# minime_2_1_1-a.net
KiCad netlist of a schematic drawn in EAGLE
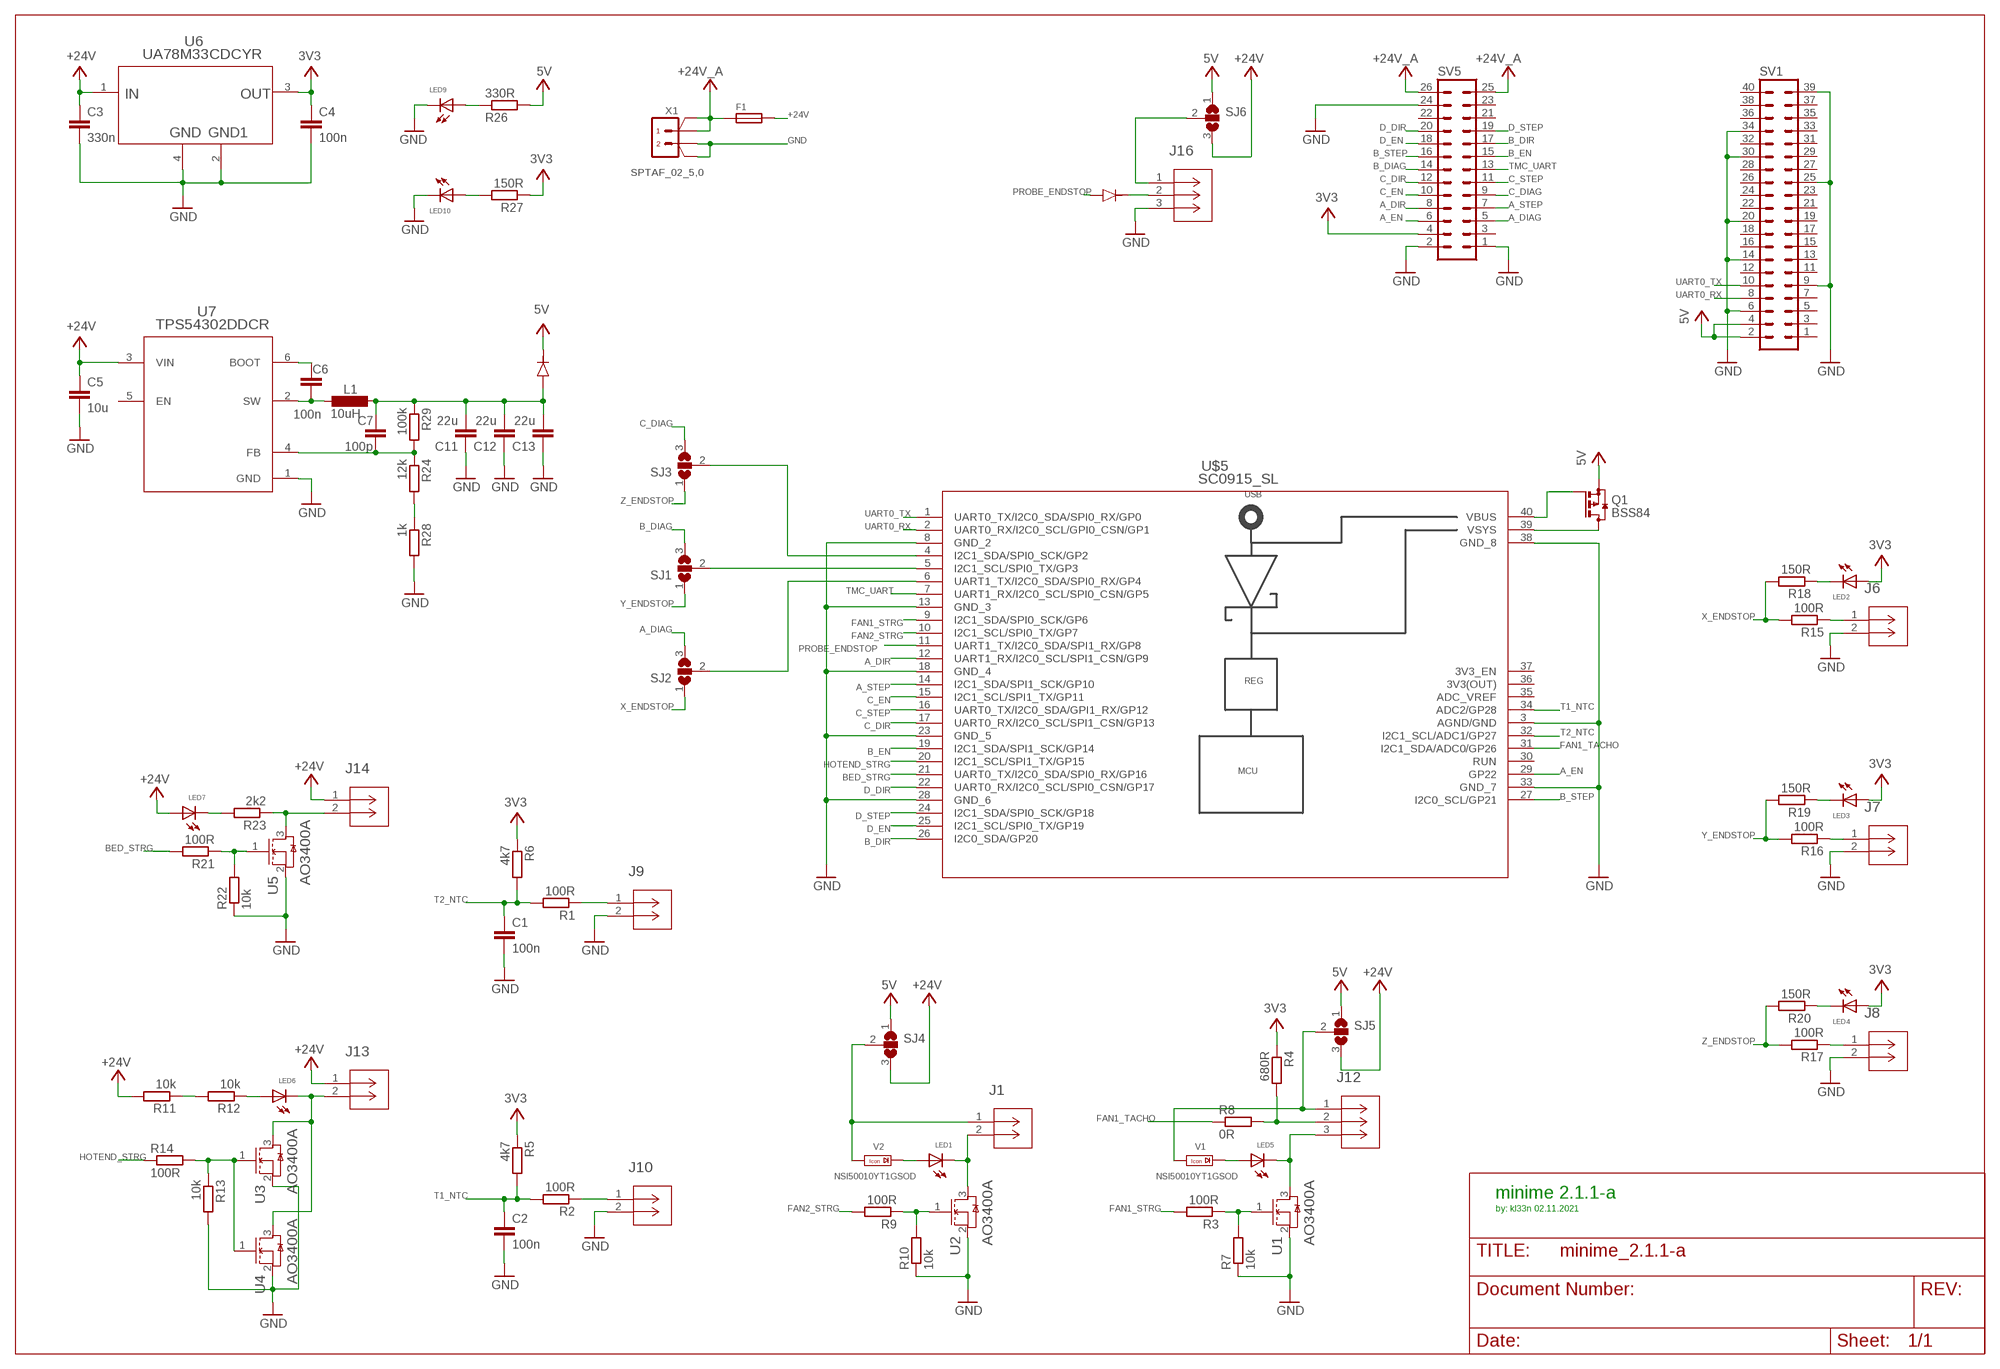
[diagram p0: schematic, sheet 1]

(export (version "E")
  (design (tool "Eeschema 10.0.6"))
  (components
    (comp (ref "C1")
      (value "100n")
      (footprint "eagle-import:C0603")
      (libsource (lib "eagle-import") (part "C-EUC0603"))
    )
    (comp (ref "C2")
      (value "100n")
      (footprint "eagle-import:C0603")
      (libsource (lib "eagle-import") (part "C-EUC0603"))
    )
    (comp (ref "C3")
      (value "330n")
      (footprint "eagle-import:C0603")
      (libsource (lib "eagle-import") (part "C-EUC0603"))
    )
    (comp (ref "C4")
      (value "100n")
      (footprint "eagle-import:C0603")
      (libsource (lib "eagle-import") (part "C-EUC0603"))
    )
    (comp (ref "C5")
      (value "10u")
      (footprint "eagle-import:C0603")
      (libsource (lib "eagle-import") (part "C-EUC0603"))
    )
    (comp (ref "C6")
      (value "100n")
      (footprint "eagle-import:C0603")
      (libsource (lib "eagle-import") (part "C-EUC0603"))
    )
    (comp (ref "C7")
      (value "100p")
      (footprint "eagle-import:C0603")
      (libsource (lib "eagle-import") (part "C-EUC0603"))
    )
    (comp (ref "C11")
      (value "22u")
      (footprint "eagle-import:C1210K")
      (libsource (lib "eagle-import") (part "C-EUC1210K"))
    )
    (comp (ref "C12")
      (value "22u")
      (footprint "eagle-import:C1210K")
      (libsource (lib "eagle-import") (part "C-EUC1210K"))
    )
    (comp (ref "C13")
      (value "22u")
      (footprint "eagle-import:C1210K")
      (libsource (lib "eagle-import") (part "C-EUC1210K"))
    )
    (comp (ref "CR1")
      (value "SS54")
      (footprint "eagle-import:DIODE_DO214AC")
      (fields
        (field (name "MANUFACTURER_PART_NUMBER") "SS14-E3/5AT")
        (field (name "COPYRIGHT") "Copyright (C) 2021 Ultra Librarian. All rights reserved.")
      )
      (libsource (lib "eagle-import") (part "SS14-E3/5AT"))
    )
    (comp (ref "CR2")
      (value "SS14")
      (footprint "eagle-import:DIODE_DO214AC")
      (fields
        (field (name "MANUFACTURER_PART_NUMBER") "SS14-E3/5AT")
        (field (name "COPYRIGHT") "Copyright (C) 2021 Ultra Librarian. All rights reserved.")
      )
      (libsource (lib "eagle-import") (part "SS14-E3/5AT"))
    )
    (comp (ref "F1")
      (value "FUSE/SERIE154")
      (footprint "eagle-import:FUSE_NANO-OMNI")
      (libsource (lib "eagle-import") (part "FUSE/SERIE154"))
    )
    (comp (ref "J1")
      (value "B2B-XH-A(LF)(SN)")
      (footprint "eagle-import:CONN_B2B-XH-A(LF)(SN)_JST")
      (fields (field (name "COPYRIGHT") "Copyright (C) 2018 Accelerated Designs. All rights reserved"))
      (libsource (lib "eagle-import") (part "B2B-XH-A(LF)(SN)"))
    )
    (comp (ref "J6")
      (value "B2B-XH-A(LF)(SN)")
      (footprint "eagle-import:CONN_B2B-XH-A(LF)(SN)_JST")
      (fields (field (name "COPYRIGHT") "Copyright (C) 2018 Accelerated Designs. All rights reserved"))
      (libsource (lib "eagle-import") (part "B2B-XH-A(LF)(SN)"))
    )
    (comp (ref "J7")
      (value "B2B-XH-A(LF)(SN)")
      (footprint "eagle-import:CONN_B2B-XH-A(LF)(SN)_JST")
      (fields (field (name "COPYRIGHT") "Copyright (C) 2018 Accelerated Designs. All rights reserved"))
      (libsource (lib "eagle-import") (part "B2B-XH-A(LF)(SN)"))
    )
    (comp (ref "J8")
      (value "B2B-XH-A(LF)(SN)")
      (footprint "eagle-import:CONN_B2B-XH-A(LF)(SN)_JST")
      (fields (field (name "COPYRIGHT") "Copyright (C) 2018 Accelerated Designs. All rights reserved"))
      (libsource (lib "eagle-import") (part "B2B-XH-A(LF)(SN)"))
    )
    (comp (ref "J9")
      (value "B2B-XH-A(LF)(SN)")
      (footprint "eagle-import:CONN_B2B-XH-A(LF)(SN)_JST")
      (fields (field (name "COPYRIGHT") "Copyright (C) 2018 Accelerated Designs. All rights reserved"))
      (libsource (lib "eagle-import") (part "B2B-XH-A(LF)(SN)"))
    )
    (comp (ref "J10")
      (value "B2B-XH-A(LF)(SN)")
      (footprint "eagle-import:CONN_B2B-XH-A(LF)(SN)_JST")
      (fields (field (name "COPYRIGHT") "Copyright (C) 2018 Accelerated Designs. All rights reserved"))
      (libsource (lib "eagle-import") (part "B2B-XH-A(LF)(SN)"))
    )
    (comp (ref "J12")
      (value "B3B-XH-A(LF)(SN)")
      (footprint "eagle-import:CONN_B3B-XH-A_JST")
      (fields (field (name "COPYRIGHT") "Copyright (C) 2018 Accelerated Designs. All rights reserved"))
      (libsource (lib "eagle-import") (part "B3B-XH-A(LF)(SN)"))
    )
    (comp (ref "J13")
      (value "B2B-XH-A(LF)(SN)")
      (footprint "eagle-import:CONN_B2B-XH-A(LF)(SN)_JST")
      (fields (field (name "COPYRIGHT") "Copyright (C) 2018 Accelerated Designs. All rights reserved"))
      (libsource (lib "eagle-import") (part "B2B-XH-A(LF)(SN)"))
    )
    (comp (ref "J14")
      (value "B2B-XH-A(LF)(SN)")
      (footprint "eagle-import:CONN_B2B-XH-A(LF)(SN)_JST")
      (fields (field (name "COPYRIGHT") "Copyright (C) 2018 Accelerated Designs. All rights reserved"))
      (libsource (lib "eagle-import") (part "B2B-XH-A(LF)(SN)"))
    )
    (comp (ref "J16")
      (value "B3B-XH-A(LF)(SN)")
      (footprint "eagle-import:CONN_B3B-XH-A_JST")
      (fields (field (name "COPYRIGHT") "Copyright (C) 2018 Accelerated Designs. All rights reserved"))
      (libsource (lib "eagle-import") (part "B3B-XH-A(LF)(SN)"))
    )
    (comp (ref "L1")
      (value "10uH")
      (footprint "eagle-import:POWER-CHOKE_WE-TPC")
      (libsource (lib "eagle-import") (part "L-EUWE-TPC"))
    )
    (comp (ref "LED1")
      (value "LEDCHIP-LED0603")
      (footprint "eagle-import:CHIP-LED0603")
      (libsource (lib "eagle-import") (part "LEDCHIP-LED0603"))
    )
    (comp (ref "LED2")
      (value "LEDCHIP-LED0603")
      (footprint "eagle-import:CHIP-LED0603")
      (libsource (lib "eagle-import") (part "LEDCHIP-LED0603"))
    )
    (comp (ref "LED3")
      (value "LEDCHIP-LED0603")
      (footprint "eagle-import:CHIP-LED0603")
      (libsource (lib "eagle-import") (part "LEDCHIP-LED0603"))
    )
    (comp (ref "LED4")
      (value "LEDCHIP-LED0603")
      (footprint "eagle-import:CHIP-LED0603")
      (libsource (lib "eagle-import") (part "LEDCHIP-LED0603"))
    )
    (comp (ref "LED5")
      (value "LEDCHIP-LED0603")
      (footprint "eagle-import:CHIP-LED0603")
      (libsource (lib "eagle-import") (part "LEDCHIP-LED0603"))
    )
    (comp (ref "LED6")
      (value "LEDCHIP-LED0603")
      (footprint "eagle-import:CHIP-LED0603")
      (libsource (lib "eagle-import") (part "LEDCHIP-LED0603"))
    )
    (comp (ref "LED7")
      (value "LEDCHIP-LED0603")
      (footprint "eagle-import:CHIP-LED0603")
      (libsource (lib "eagle-import") (part "LEDCHIP-LED0603"))
    )
    (comp (ref "LED9")
      (value "LEDCHIP-LED0603")
      (footprint "eagle-import:CHIP-LED0603")
      (libsource (lib "eagle-import") (part "LEDCHIP-LED0603"))
    )
    (comp (ref "LED10")
      (value "LEDCHIP-LED0603")
      (footprint "eagle-import:CHIP-LED0603")
      (libsource (lib "eagle-import") (part "LEDCHIP-LED0603"))
    )
    (comp (ref "Q1")
      (value "BSS84")
      (footprint "eagle-import:SOT23")
      (libsource (lib "eagle-import") (part "BSS84"))
    )
    (comp (ref "R1")
      (value "100R")
      (footprint "eagle-import:R0603")
      (libsource (lib "eagle-import") (part "R-EU_R0603"))
    )
    (comp (ref "R2")
      (value "100R")
      (footprint "eagle-import:R0603")
      (libsource (lib "eagle-import") (part "R-EU_R0603"))
    )
    (comp (ref "R3")
      (value "100R")
      (footprint "eagle-import:R0603")
      (libsource (lib "eagle-import") (part "R-EU_R0603"))
    )
    (comp (ref "R4")
      (value "680R")
      (footprint "eagle-import:R0603")
      (libsource (lib "eagle-import") (part "R-EU_R0603"))
    )
    (comp (ref "R5")
      (value "4k7")
      (footprint "eagle-import:R0603")
      (libsource (lib "eagle-import") (part "R-EU_R0603"))
    )
    (comp (ref "R6")
      (value "4k7")
      (footprint "eagle-import:R0603")
      (libsource (lib "eagle-import") (part "R-EU_R0603"))
    )
    (comp (ref "R7")
      (value "10k")
      (footprint "eagle-import:R0603")
      (libsource (lib "eagle-import") (part "R-EU_R0603"))
    )
    (comp (ref "R8")
      (value "0R")
      (footprint "eagle-import:R0603")
      (libsource (lib "eagle-import") (part "R-EU_R0603"))
    )
    (comp (ref "R9")
      (value "100R")
      (footprint "eagle-import:R0603")
      (libsource (lib "eagle-import") (part "R-EU_R0603"))
    )
    (comp (ref "R10")
      (value "10k")
      (footprint "eagle-import:R0603")
      (libsource (lib "eagle-import") (part "R-EU_R0603"))
    )
    (comp (ref "R11")
      (value "10k")
      (footprint "eagle-import:R0603")
      (libsource (lib "eagle-import") (part "R-EU_R0603"))
    )
    (comp (ref "R12")
      (value "10k")
      (footprint "eagle-import:R0603")
      (libsource (lib "eagle-import") (part "R-EU_R0603"))
    )
    (comp (ref "R13")
      (value "10k")
      (footprint "eagle-import:R0603")
      (libsource (lib "eagle-import") (part "R-EU_R0603"))
    )
    (comp (ref "R14")
      (value "100R")
      (footprint "eagle-import:R0603")
      (libsource (lib "eagle-import") (part "R-EU_R0603"))
    )
    (comp (ref "R15")
      (value "100R")
      (footprint "eagle-import:R0603")
      (libsource (lib "eagle-import") (part "R-EU_R0603"))
    )
    (comp (ref "R16")
      (value "100R")
      (footprint "eagle-import:R0603")
      (libsource (lib "eagle-import") (part "R-EU_R0603"))
    )
    (comp (ref "R17")
      (value "100R")
      (footprint "eagle-import:R0603")
      (libsource (lib "eagle-import") (part "R-EU_R0603"))
    )
    (comp (ref "R18")
      (value "150R")
      (footprint "eagle-import:R0603")
      (libsource (lib "eagle-import") (part "R-EU_R0603"))
    )
    (comp (ref "R19")
      (value "150R")
      (footprint "eagle-import:R0603")
      (libsource (lib "eagle-import") (part "R-EU_R0603"))
    )
    (comp (ref "R20")
      (value "150R")
      (footprint "eagle-import:R0603")
      (libsource (lib "eagle-import") (part "R-EU_R0603"))
    )
    (comp (ref "R21")
      (value "100R")
      (footprint "eagle-import:R0603")
      (libsource (lib "eagle-import") (part "R-EU_R0603"))
    )
    (comp (ref "R22")
      (value "10k")
      (footprint "eagle-import:R0603")
      (libsource (lib "eagle-import") (part "R-EU_R0603"))
    )
    (comp (ref "R23")
      (value "2k2")
      (footprint "eagle-import:R0603")
      (libsource (lib "eagle-import") (part "R-EU_R0603"))
    )
    (comp (ref "R24")
      (value "12k")
      (footprint "eagle-import:R0603")
      (libsource (lib "eagle-import") (part "R-EU_R0603"))
    )
    (comp (ref "R26")
      (value "330R")
      (footprint "eagle-import:R0603")
      (libsource (lib "eagle-import") (part "R-EU_R0603"))
    )
    (comp (ref "R27")
      (value "150R")
      (footprint "eagle-import:R0603")
      (libsource (lib "eagle-import") (part "R-EU_R0603"))
    )
    (comp (ref "R28")
      (value "1k")
      (footprint "eagle-import:R0603")
      (libsource (lib "eagle-import") (part "R-EU_R0603"))
    )
    (comp (ref "R29")
      (value "100k")
      (footprint "eagle-import:R0603")
      (libsource (lib "eagle-import") (part "R-EU_R0603"))
    )
    (comp (ref "SJ1")
      (value "SJ2W")
      (footprint "eagle-import:SJ_2")
      (libsource (lib "eagle-import") (part "SJ2W"))
    )
    (comp (ref "SJ2")
      (value "SJ2W")
      (footprint "eagle-import:SJ_2")
      (libsource (lib "eagle-import") (part "SJ2W"))
    )
    (comp (ref "SJ3")
      (value "SJ2W")
      (footprint "eagle-import:SJ_2")
      (libsource (lib "eagle-import") (part "SJ2W"))
    )
    (comp (ref "SJ4")
      (value "SJ2W")
      (footprint "eagle-import:SJ_2")
      (libsource (lib "eagle-import") (part "SJ2W"))
    )
    (comp (ref "SJ5")
      (value "SJ2W")
      (footprint "eagle-import:SJ_2")
      (libsource (lib "eagle-import") (part "SJ2W"))
    )
    (comp (ref "SJ6")
      (value "SJ2W")
      (footprint "eagle-import:SJ_2")
      (libsource (lib "eagle-import") (part "SJ2W"))
    )
    (comp (ref "SV1")
      (value "MA20-2")
      (footprint "eagle-import:MA20-2")
      (libsource (lib "eagle-import") (part "MA20-2"))
    )
    (comp (ref "SV5")
      (value "MA13-2")
      (footprint "eagle-import:MA13-2")
      (libsource (lib "eagle-import") (part "MA13-2"))
    )
    (comp (ref "U$5")
      (value "SC0915_SL")
      (footprint "eagle-import:STIFTLEISTE")
      (libsource (lib "eagle-import") (part "SC0915_SL"))
    )
    (comp (ref "U1")
      (value "AO3400A")
      (footprint "eagle-import:SOT-23-3L_AOS")
      (fields (field (name "COPYRIGHT") "Copyright (C) 2018 Accelerated Designs. All rights reserved"))
      (libsource (lib "eagle-import") (part "AO3400A"))
    )
    (comp (ref "U2")
      (value "AO3400A")
      (footprint "eagle-import:SOT-23-3L_AOS")
      (fields (field (name "COPYRIGHT") "Copyright (C) 2018 Accelerated Designs. All rights reserved"))
      (libsource (lib "eagle-import") (part "AO3400A"))
    )
    (comp (ref "U3")
      (value "AO3400A")
      (footprint "eagle-import:SOT-23-3L_AOS")
      (fields (field (name "COPYRIGHT") "Copyright (C) 2018 Accelerated Designs. All rights reserved"))
      (libsource (lib "eagle-import") (part "AO3400A"))
    )
    (comp (ref "U4")
      (value "AO3400A")
      (footprint "eagle-import:SOT-23-3L_AOS")
      (fields (field (name "COPYRIGHT") "Copyright (C) 2018 Accelerated Designs. All rights reserved"))
      (libsource (lib "eagle-import") (part "AO3400A"))
    )
    (comp (ref "U5")
      (value "AO3400A")
      (footprint "eagle-import:SOT-23-3L_AOS")
      (fields (field (name "COPYRIGHT") "Copyright (C) 2018 Accelerated Designs. All rights reserved"))
      (libsource (lib "eagle-import") (part "AO3400A"))
    )
    (comp (ref "U6")
      (value "UA78M33CDCYR")
      (footprint "eagle-import:DCY0004A_N")
      (fields (field (name "COPYRIGHT") "Copyright (C) 2021 Ultra Librarian. All rights reserved."))
      (libsource (lib "eagle-import") (part "UA78M33CDCYR"))
    )
    (comp (ref "U7")
      (value "TPS54302DDCR")
      (footprint "eagle-import:DDC0006A_N")
      (fields (field (name "COPYRIGHT") "Copyright (C) 2021 Ultra Librarian. All rights reserved."))
      (libsource (lib "eagle-import") (part "TPS54302DDCR"))
    )
    (comp (ref "V1")
      (value "NSI50010YT1GSOD")
      (footprint "eagle-import:SOD123")
      (libsource (lib "eagle-import") (part "NSI50010YT1GSOD"))
    )
    (comp (ref "V2")
      (value "NSI50010YT1GSOD")
      (footprint "eagle-import:SOD123")
      (libsource (lib "eagle-import") (part "NSI50010YT1GSOD"))
    )
    (comp (ref "X1")
      (value "SPTAF_02_5,0")
      (footprint "eagle-import:5-2")
      (libsource (lib "eagle-import") (part "SPTAF_02_5,0"))
    )
  )
  (nets
    (net (code "1") (name "+24V") (class "Default")
      (node (ref "C3") (pin "1") (pinfunction "1_1") (pintype "passive"))
      (node (ref "C5") (pin "1") (pinfunction "1_1") (pintype "passive"))
      (node (ref "F1") (pin "2") (pinfunction "2_2") (pintype "passive"))
      (node (ref "J13") (pin "1") (pinfunction "1_1") (pintype "passive"))
      (node (ref "J14") (pin "1") (pinfunction "1_1") (pintype "passive"))
      (node (ref "LED7") (pin "A") (pinfunction "A_A") (pintype "passive"))
      (node (ref "R11") (pin "2") (pinfunction "2_2") (pintype "passive"))
      (node (ref "SJ4") (pin "3") (pinfunction "3_3") (pintype "passive"))
      (node (ref "SJ5") (pin "3") (pinfunction "3_3") (pintype "passive"))
      (node (ref "SJ6") (pin "3") (pinfunction "3_3") (pintype "passive"))
      (node (ref "U6") (pin "1") (pinfunction "INPUT_1") (pintype "power_in"))
      (node (ref "U7") (pin "3") (pinfunction "VIN_3") (pintype "power_in"))
    )
    (net (code "2") (name "+24V_A") (class "Default")
      (node (ref "F1") (pin "1") (pinfunction "1_1") (pintype "passive"))
      (node (ref "SV5") (pin "25") (pinfunction "25_25") (pintype "passive"))
      (node (ref "SV5") (pin "26") (pinfunction "26_26") (pintype "passive"))
      (node (ref "X1") (pin "1") (pinfunction "1_1") (pintype "passive"))
      (node (ref "X1") (pin "1A") (pinfunction "1A_1A") (pintype "passive"))
    )
    (net (code "3") (name "/3V3_EN") (class "Default")
      (node (ref "U$5") (pin "37") (pinfunction "3V3_EN_37") (pintype "power_in"))
    )
    (net (code "4") (name "/ADC_VREF") (class "Default")
      (node (ref "U$5") (pin "35") (pinfunction "ADC_VREF_35") (pintype "power_in"))
    )
    (net (code "5") (name "/A_DIAG") (class "Default")
      (node (ref "SJ2") (pin "3") (pinfunction "3_3") (pintype "passive"))
      (node (ref "SV5") (pin "5") (pinfunction "5_5") (pintype "passive"))
    )
    (net (code "6") (name "/A_DIR") (class "Default")
      (node (ref "SV5") (pin "8") (pinfunction "8_8") (pintype "passive"))
      (node (ref "U$5") (pin "12") (pinfunction "UART1_RX/I2C0_SCL/SPI1_CSN/GP9_12") (pintype "bidirectional"))
    )
    (net (code "7") (name "/A_EN") (class "Default")
      (node (ref "SV5") (pin "6") (pinfunction "6_6") (pintype "passive"))
      (node (ref "U$5") (pin "29") (pinfunction "GP22_29") (pintype "bidirectional"))
    )
    (net (code "8") (name "/A_STEP") (class "Default")
      (node (ref "SV5") (pin "7") (pinfunction "7_7") (pintype "passive"))
      (node (ref "U$5") (pin "14") (pinfunction "I2C1_SDA/SPI1_SCK/GP10_14") (pintype "bidirectional"))
    )
    (net (code "9") (name "/BED_STRG") (class "Default")
      (node (ref "R21") (pin "2") (pinfunction "2_2") (pintype "passive"))
      (node (ref "U$5") (pin "21") (pinfunction "UART0_TX/I2C0_SDA/SPI0_RX/GP16_21") (pintype "bidirectional"))
    )
    (net (code "10") (name "/B_DIAG") (class "Default")
      (node (ref "SJ1") (pin "3") (pinfunction "3_3") (pintype "passive"))
      (node (ref "SV5") (pin "14") (pinfunction "14_14") (pintype "passive"))
    )
    (net (code "11") (name "/B_DIR") (class "Default")
      (node (ref "SV5") (pin "17") (pinfunction "17_17") (pintype "passive"))
      (node (ref "U$5") (pin "26") (pinfunction "I2C0_SDA/GP20_26") (pintype "bidirectional"))
    )
    (net (code "12") (name "/B_EN") (class "Default")
      (node (ref "SV5") (pin "15") (pinfunction "15_15") (pintype "passive"))
      (node (ref "U$5") (pin "19") (pinfunction "I2C1_SDA/SPI1_SCK/GP14_19") (pintype "bidirectional"))
    )
    (net (code "13") (name "/B_STEP") (class "Default")
      (node (ref "SV5") (pin "16") (pinfunction "16_16") (pintype "passive"))
      (node (ref "U$5") (pin "27") (pinfunction "I2C0_SCL/GP21_27") (pintype "bidirectional"))
    )
    (net (code "14") (name "/C_DIAG") (class "Default")
      (node (ref "SJ3") (pin "3") (pinfunction "3_3") (pintype "passive"))
      (node (ref "SV5") (pin "9") (pinfunction "9_9") (pintype "passive"))
    )
    (net (code "15") (name "/C_DIR") (class "Default")
      (node (ref "SV5") (pin "12") (pinfunction "12_12") (pintype "passive"))
      (node (ref "U$5") (pin "17") (pinfunction "UART0_RX/I2C0_SCL/SPI1_CSN/GP13_17") (pintype "bidirectional"))
    )
    (net (code "16") (name "/C_EN") (class "Default")
      (node (ref "SV5") (pin "10") (pinfunction "10_10") (pintype "passive"))
      (node (ref "U$5") (pin "15") (pinfunction "I2C1_SCL/SPI1_TX/GP11_15") (pintype "bidirectional"))
    )
    (net (code "17") (name "/C_STEP") (class "Default")
      (node (ref "SV5") (pin "11") (pinfunction "11_11") (pintype "passive"))
      (node (ref "U$5") (pin "16") (pinfunction "UART0_TX/I2C0_SDA/GPI1_RX/GP12_16") (pintype "bidirectional"))
    )
    (net (code "18") (name "/D_DIR") (class "Default")
      (node (ref "SV5") (pin "20") (pinfunction "20_20") (pintype "passive"))
      (node (ref "U$5") (pin "22") (pinfunction "UART0_RX/I2C0_SCL/SPI0_CSN/GP17_22") (pintype "bidirectional"))
    )
    (net (code "19") (name "/D_EN") (class "Default")
      (node (ref "SV5") (pin "18") (pinfunction "18_18") (pintype "passive"))
      (node (ref "U$5") (pin "25") (pinfunction "I2C1_SCL/SPI0_TX/GP19_25") (pintype "bidirectional"))
    )
    (net (code "20") (name "/D_STEP") (class "Default")
      (node (ref "SV5") (pin "19") (pinfunction "19_19") (pintype "passive"))
      (node (ref "U$5") (pin "24") (pinfunction "I2C1_SDA/SPI0_SCK/GP18_24") (pintype "bidirectional"))
    )
    (net (code "21") (name "/FAN1_STRG") (class "Default")
      (node (ref "R3") (pin "2") (pinfunction "2_2") (pintype "passive"))
      (node (ref "U$5") (pin "9") (pinfunction "I2C1_SDA/SPI0_SCK/GP6_9") (pintype "bidirectional"))
    )
    (net (code "22") (name "/FAN1_TACHO") (class "Default")
      (node (ref "R8") (pin "1") (pinfunction "1_1") (pintype "passive"))
      (node (ref "U$5") (pin "31") (pinfunction "I2C1_SDA/ADC0/GP26_31") (pintype "bidirectional"))
    )
    (net (code "23") (name "/FAN2_STRG") (class "Default")
      (node (ref "R9") (pin "2") (pinfunction "2_2") (pintype "passive"))
      (node (ref "U$5") (pin "10") (pinfunction "I2C1_SCL/SPI0_TX/GP7_10") (pintype "bidirectional"))
    )
    (net (code "24") (name "/HOTEND_STRG") (class "Default")
      (node (ref "R14") (pin "1") (pinfunction "1_1") (pintype "passive"))
      (node (ref "U$5") (pin "20") (pinfunction "I2C1_SCL/SPI1_TX/GP15_20") (pintype "bidirectional"))
    )
    (net (code "25") (name "/PROBE_ENDSTOP") (class "Default")
      (node (ref "CR2") (pin "2") (pinfunction "2_2") (pintype "passive"))
      (node (ref "U$5") (pin "11") (pinfunction "UART1_TX/I2C0_SDA/SPI1_RX/GP8_11") (pintype "bidirectional"))
    )
    (net (code "26") (name "/T1_NTC") (class "Default")
      (node (ref "C2") (pin "1") (pinfunction "1_1") (pintype "passive"))
      (node (ref "R2") (pin "2") (pinfunction "2_2") (pintype "passive"))
      (node (ref "R5") (pin "2") (pinfunction "2_2") (pintype "passive"))
      (node (ref "U$5") (pin "34") (pinfunction "ADC2/GP28_34") (pintype "bidirectional"))
    )
    (net (code "27") (name "/T2_NTC") (class "Default")
      (node (ref "C1") (pin "1") (pinfunction "1_1") (pintype "passive"))
      (node (ref "R1") (pin "2") (pinfunction "2_2") (pintype "passive"))
      (node (ref "R6") (pin "2") (pinfunction "2_2") (pintype "passive"))
      (node (ref "U$5") (pin "32") (pinfunction "I2C1_SCL/ADC1/GP27_32") (pintype "bidirectional"))
    )
    (net (code "28") (name "/TMC_UART") (class "Default")
      (node (ref "SV5") (pin "13") (pinfunction "13_13") (pintype "passive"))
      (node (ref "U$5") (pin "7") (pinfunction "UART1_RX/I2C0_SCL/SPI0_CSN/GP5_7") (pintype "bidirectional"))
    )
    (net (code "29") (name "/UART0_RX") (class "Default")
      (node (ref "SV1") (pin "8") (pinfunction "8_8") (pintype "passive"))
      (node (ref "U$5") (pin "2") (pinfunction "UART0_RX/I2C0_SCL/GPI0_CSN/GP1_2") (pintype "bidirectional"))
    )
    (net (code "30") (name "/UART0_TX") (class "Default")
      (node (ref "SV1") (pin "10") (pinfunction "10_10") (pintype "passive"))
      (node (ref "U$5") (pin "1") (pinfunction "UART0_TX/I2C0_SDA/SPI0_RX/GP0_1") (pintype "bidirectional"))
    )
    (net (code "31") (name "/X_ENDSTOP") (class "Default")
      (node (ref "R15") (pin "2") (pinfunction "2_2") (pintype "passive"))
      (node (ref "R18") (pin "2") (pinfunction "2_2") (pintype "passive"))
      (node (ref "SJ2") (pin "1") (pinfunction "1_1") (pintype "passive"))
    )
    (net (code "32") (name "/Y_ENDSTOP") (class "Default")
      (node (ref "R16") (pin "2") (pinfunction "2_2") (pintype "passive"))
      (node (ref "R19") (pin "2") (pinfunction "2_2") (pintype "passive"))
      (node (ref "SJ1") (pin "1") (pinfunction "1_1") (pintype "passive"))
    )
    (net (code "33") (name "/Z_ENDSTOP") (class "Default")
      (node (ref "R17") (pin "2") (pinfunction "2_2") (pintype "passive"))
      (node (ref "R20") (pin "2") (pinfunction "2_2") (pintype "passive"))
      (node (ref "SJ3") (pin "1") (pinfunction "1_1") (pintype "passive"))
    )
    (net (code "34") (name "3V3") (class "Default")
      (node (ref "C4") (pin "1") (pinfunction "1_1") (pintype "passive"))
      (node (ref "LED2") (pin "A") (pinfunction "A_A") (pintype "passive"))
      (node (ref "LED3") (pin "A") (pinfunction "A_A") (pintype "passive"))
      (node (ref "LED4") (pin "A") (pinfunction "A_A") (pintype "passive"))
      (node (ref "R27") (pin "1") (pinfunction "1_1") (pintype "passive"))
      (node (ref "R4") (pin "1") (pinfunction "1_1") (pintype "passive"))
      (node (ref "R5") (pin "1") (pinfunction "1_1") (pintype "passive"))
      (node (ref "R6") (pin "1") (pinfunction "1_1") (pintype "passive"))
      (node (ref "SV5") (pin "4") (pinfunction "4_4") (pintype "passive"))
      (node (ref "U6") (pin "3") (pinfunction "OUTPUT_3") (pintype "power_in"))
    )
    (net (code "35") (name "5V") (class "Default")
      (node (ref "CR1") (pin "1") (pinfunction "1_1") (pintype "passive"))
      (node (ref "Q1") (pin "2") (pinfunction "S_2") (pintype "passive"))
      (node (ref "R26") (pin "2") (pinfunction "2_2") (pintype "passive"))
      (node (ref "SJ4") (pin "1") (pinfunction "1_1") (pintype "passive"))
      (node (ref "SJ5") (pin "1") (pinfunction "1_1") (pintype "passive"))
      (node (ref "SJ6") (pin "1") (pinfunction "1_1") (pintype "passive"))
      (node (ref "SV1") (pin "2") (pinfunction "2_2") (pintype "passive"))
      (node (ref "SV1") (pin "4") (pinfunction "4_4") (pintype "passive"))
    )
    (net (code "36") (name "GND") (class "Default")
      (node (ref "C1") (pin "2") (pinfunction "2_2") (pintype "passive"))
      (node (ref "C11") (pin "1") (pinfunction "1_1") (pintype "passive"))
      (node (ref "C12") (pin "1") (pinfunction "1_1") (pintype "passive"))
      (node (ref "C13") (pin "1") (pinfunction "1_1") (pintype "passive"))
      (node (ref "C2") (pin "2") (pinfunction "2_2") (pintype "passive"))
      (node (ref "C3") (pin "2") (pinfunction "2_2") (pintype "passive"))
      (node (ref "C4") (pin "2") (pinfunction "2_2") (pintype "passive"))
      (node (ref "C5") (pin "2") (pinfunction "2_2") (pintype "passive"))
      (node (ref "J10") (pin "2") (pinfunction "2_2") (pintype "passive"))
      (node (ref "J16") (pin "3") (pinfunction "3_3") (pintype "passive"))
      (node (ref "J6") (pin "2") (pinfunction "2_2") (pintype "passive"))
      (node (ref "J7") (pin "2") (pinfunction "2_2") (pintype "passive"))
      (node (ref "J8") (pin "2") (pinfunction "2_2") (pintype "passive"))
      (node (ref "J9") (pin "2") (pinfunction "2_2") (pintype "passive"))
      (node (ref "LED10") (pin "C") (pinfunction "C_C") (pintype "passive"))
      (node (ref "LED9") (pin "C") (pinfunction "C_C") (pintype "passive"))
      (node (ref "R10") (pin "1") (pinfunction "1_1") (pintype "passive"))
      (node (ref "R13") (pin "2") (pinfunction "2_2") (pintype "passive"))
      (node (ref "R22") (pin "1") (pinfunction "1_1") (pintype "passive"))
      (node (ref "R28") (pin "2") (pinfunction "2_2") (pintype "passive"))
      (node (ref "R7") (pin "1") (pinfunction "1_1") (pintype "passive"))
      (node (ref "SV1") (pin "14") (pinfunction "14_14") (pintype "passive"))
      (node (ref "SV1") (pin "20") (pinfunction "20_20") (pintype "passive"))
      (node (ref "SV1") (pin "25") (pinfunction "25_25") (pintype "passive"))
      (node (ref "SV1") (pin "30") (pinfunction "30_30") (pintype "passive"))
      (node (ref "SV1") (pin "34") (pinfunction "34_34") (pintype "passive"))
      (node (ref "SV1") (pin "39") (pinfunction "39_39") (pintype "passive"))
      (node (ref "SV1") (pin "6") (pinfunction "6_6") (pintype "passive"))
      (node (ref "SV1") (pin "9") (pinfunction "9_9") (pintype "passive"))
      (node (ref "SV5") (pin "1") (pinfunction "1_1") (pintype "passive"))
      (node (ref "SV5") (pin "2") (pinfunction "2_2") (pintype "passive"))
      (node (ref "SV5") (pin "24") (pinfunction "24_24") (pintype "passive"))
      (node (ref "U$5") (pin "13") (pinfunction "GND_3_13") (pintype "passive"))
      (node (ref "U$5") (pin "18") (pinfunction "GND_4_18") (pintype "passive"))
      (node (ref "U$5") (pin "23") (pinfunction "GND_5_23") (pintype "passive"))
      (node (ref "U$5") (pin "28") (pinfunction "GND_6_28") (pintype "passive"))
      (node (ref "U$5") (pin "3") (pinfunction "AGND/GND_3") (pintype "passive"))
      (node (ref "U$5") (pin "33") (pinfunction "GND_7_33") (pintype "passive"))
      (node (ref "U$5") (pin "38") (pinfunction "GND_8_38") (pintype "passive"))
      (node (ref "U$5") (pin "8") (pinfunction "GND_2_8") (pintype "passive"))
      (node (ref "U1") (pin "2") (pinfunction "S_2") (pintype "passive"))
      (node (ref "U2") (pin "2") (pinfunction "S_2") (pintype "passive"))
      (node (ref "U3") (pin "2") (pinfunction "S_2") (pintype "passive"))
      (node (ref "U4") (pin "2") (pinfunction "S_2") (pintype "passive"))
      (node (ref "U5") (pin "2") (pinfunction "S_2") (pintype "passive"))
      (node (ref "U6") (pin "2") (pinfunction "COMMON_2_2") (pintype "power_in"))
      (node (ref "U6") (pin "4") (pinfunction "COMMON_4") (pintype "power_in"))
      (node (ref "U7") (pin "1") (pinfunction "GND_1") (pintype "power_in"))
      (node (ref "X1") (pin "2") (pinfunction "2_2") (pintype "passive"))
      (node (ref "X1") (pin "2A") (pinfunction "2A_2A") (pintype "passive"))
    )
    (net (code "37") (name "Net-(C11-Pad2)") (class "Default")
      (node (ref "C11") (pin "2") (pinfunction "2_2") (pintype "passive"))
      (node (ref "C12") (pin "2") (pinfunction "2_2") (pintype "passive"))
      (node (ref "C13") (pin "2") (pinfunction "2_2") (pintype "passive"))
      (node (ref "C7") (pin "1") (pinfunction "1_1") (pintype "passive"))
      (node (ref "CR1") (pin "2") (pinfunction "2_2") (pintype "passive"))
      (node (ref "L1") (pin "1") (pinfunction "1_1") (pintype "passive"))
      (node (ref "R29") (pin "1") (pinfunction "1_1") (pintype "passive"))
    )
    (net (code "38") (name "Net-(CR2-Pad1)") (class "Default")
      (node (ref "CR2") (pin "1") (pinfunction "1_1") (pintype "passive"))
      (node (ref "J16") (pin "2") (pinfunction "2_2") (pintype "passive"))
    )
    (net (code "39") (name "Net-(J1-Pad1)") (class "Default")
      (node (ref "J1") (pin "1") (pinfunction "1_1") (pintype "passive"))
      (node (ref "SJ4") (pin "2") (pinfunction "2_2") (pintype "passive"))
      (node (ref "V2") (pin "A") (pinfunction "A_A") (pintype "bidirectional"))
    )
    (net (code "40") (name "Net-(J6-Pad1)") (class "Default")
      (node (ref "J6") (pin "1") (pinfunction "1_1") (pintype "passive"))
      (node (ref "R15") (pin "1") (pinfunction "1_1") (pintype "passive"))
    )
    (net (code "41") (name "Net-(J7-Pad1)") (class "Default")
      (node (ref "J7") (pin "1") (pinfunction "1_1") (pintype "passive"))
      (node (ref "R16") (pin "1") (pinfunction "1_1") (pintype "passive"))
    )
    (net (code "42") (name "Net-(J8-Pad1)") (class "Default")
      (node (ref "J8") (pin "1") (pinfunction "1_1") (pintype "passive"))
      (node (ref "R17") (pin "1") (pinfunction "1_1") (pintype "passive"))
    )
    (net (code "43") (name "Net-(J9-Pad1)") (class "Default")
      (node (ref "J9") (pin "1") (pinfunction "1_1") (pintype "passive"))
      (node (ref "R1") (pin "1") (pinfunction "1_1") (pintype "passive"))
    )
    (net (code "44") (name "Net-(J10-Pad1)") (class "Default")
      (node (ref "J10") (pin "1") (pinfunction "1_1") (pintype "passive"))
      (node (ref "R2") (pin "1") (pinfunction "1_1") (pintype "passive"))
    )
    (net (code "45") (name "Net-(J12-Pad1)") (class "Default")
      (node (ref "J12") (pin "1") (pinfunction "1_1") (pintype "passive"))
      (node (ref "SJ5") (pin "2") (pinfunction "2_2") (pintype "passive"))
      (node (ref "V1") (pin "A") (pinfunction "A_A") (pintype "bidirectional"))
    )
    (net (code "46") (name "Net-(J12-Pad2)") (class "Default")
      (node (ref "J12") (pin "2") (pinfunction "2_2") (pintype "passive"))
      (node (ref "R4") (pin "2") (pinfunction "2_2") (pintype "passive"))
      (node (ref "R8") (pin "2") (pinfunction "2_2") (pintype "passive"))
    )
    (net (code "47") (name "Net-(J16-Pad1)") (class "Default")
      (node (ref "J16") (pin "1") (pinfunction "1_1") (pintype "passive"))
      (node (ref "SJ6") (pin "2") (pinfunction "2_2") (pintype "passive"))
    )
    (net (code "48") (name "Net-(LED2-PadC)") (class "Default")
      (node (ref "LED2") (pin "C") (pinfunction "C_C") (pintype "passive"))
      (node (ref "R18") (pin "1") (pinfunction "1_1") (pintype "passive"))
    )
    (net (code "49") (name "Net-(LED3-PadC)") (class "Default")
      (node (ref "LED3") (pin "C") (pinfunction "C_C") (pintype "passive"))
      (node (ref "R19") (pin "1") (pinfunction "1_1") (pintype "passive"))
    )
    (net (code "50") (name "Net-(LED4-PadC)") (class "Default")
      (node (ref "LED4") (pin "C") (pinfunction "C_C") (pintype "passive"))
      (node (ref "R20") (pin "1") (pinfunction "1_1") (pintype "passive"))
    )
    (net (code "51") (name "Net-(LED6-PadA)") (class "Default")
      (node (ref "LED6") (pin "A") (pinfunction "A_A") (pintype "passive"))
      (node (ref "R12") (pin "1") (pinfunction "1_1") (pintype "passive"))
    )
    (net (code "52") (name "Net-(LED7-PadC)") (class "Default")
      (node (ref "LED7") (pin "C") (pinfunction "C_C") (pintype "passive"))
      (node (ref "R23") (pin "2") (pinfunction "2_2") (pintype "passive"))
    )
    (net (code "53") (name "Net-(LED9-PadA)") (class "Default")
      (node (ref "LED9") (pin "A") (pinfunction "A_A") (pintype "passive"))
      (node (ref "R26") (pin "1") (pinfunction "1_1") (pintype "passive"))
    )
    (net (code "54") (name "Net-(LED10-PadA)") (class "Default")
      (node (ref "LED10") (pin "A") (pinfunction "A_A") (pintype "passive"))
      (node (ref "R27") (pin "2") (pinfunction "2_2") (pintype "passive"))
    )
    (net (code "55") (name "Net-(Q1-D)") (class "Default")
      (node (ref "Q1") (pin "3") (pinfunction "D_3") (pintype "passive"))
      (node (ref "U$5") (pin "39") (pinfunction "VSYS_39") (pintype "power_in"))
    )
    (net (code "56") (name "Net-(Q1-G)") (class "Default")
      (node (ref "Q1") (pin "1") (pinfunction "G_1") (pintype "passive"))
      (node (ref "U$5") (pin "40") (pinfunction "VBUS_40") (pintype "power_in"))
    )
    (net (code "57") (name "Net-(R11-Pad1)") (class "Default")
      (node (ref "R11") (pin "1") (pinfunction "1_1") (pintype "passive"))
      (node (ref "R12") (pin "2") (pinfunction "2_2") (pintype "passive"))
    )
    (net (code "58") (name "Net-(R24-Pad2)") (class "Default")
      (node (ref "R24") (pin "2") (pinfunction "2_2") (pintype "passive"))
      (node (ref "R28") (pin "1") (pinfunction "1_1") (pintype "passive"))
    )
    (net (code "59") (name "Net-(U$5-I2C1_SCL{slash}SPI0_TX{slash}GP3)") (class "Default")
      (node (ref "SJ1") (pin "2") (pinfunction "2_2") (pintype "passive"))
      (node (ref "U$5") (pin "5") (pinfunction "I2C1_SCL/SPI0_TX/GP3_5") (pintype "bidirectional"))
    )
    (net (code "60") (name "Net-(U$5-I2C1_SDA{slash}SPI0_SCK{slash}GP2)") (class "Default")
      (node (ref "SJ3") (pin "2") (pinfunction "2_2") (pintype "passive"))
      (node (ref "U$5") (pin "4") (pinfunction "I2C1_SDA/SPI0_SCK/GP2_4") (pintype "bidirectional"))
    )
    (net (code "61") (name "Net-(U$5-UART1_TX{slash}I2C0_SDA{slash}SPI0_RX{slash}GP4)") (class "Default")
      (node (ref "SJ2") (pin "2") (pinfunction "2_2") (pintype "passive"))
      (node (ref "U$5") (pin "6") (pinfunction "UART1_TX/I2C0_SDA/SPI0_RX/GP4_6") (pintype "bidirectional"))
    )
    (net (code "62") (name "Net-(U1-D)") (class "Default")
      (node (ref "J12") (pin "3") (pinfunction "3_3") (pintype "passive"))
      (node (ref "LED5") (pin "C") (pinfunction "C_C") (pintype "passive"))
      (node (ref "U1") (pin "3") (pinfunction "D_3") (pintype "passive"))
    )
    (net (code "63") (name "Net-(U1-G)") (class "Default")
      (node (ref "R3") (pin "1") (pinfunction "1_1") (pintype "passive"))
      (node (ref "R7") (pin "2") (pinfunction "2_2") (pintype "passive"))
      (node (ref "U1") (pin "1") (pinfunction "G_1") (pintype "passive"))
    )
    (net (code "64") (name "Net-(U2-D)") (class "Default")
      (node (ref "J1") (pin "2") (pinfunction "2_2") (pintype "passive"))
      (node (ref "LED1") (pin "C") (pinfunction "C_C") (pintype "passive"))
      (node (ref "U2") (pin "3") (pinfunction "D_3") (pintype "passive"))
    )
    (net (code "65") (name "Net-(U2-G)") (class "Default")
      (node (ref "R10") (pin "2") (pinfunction "2_2") (pintype "passive"))
      (node (ref "R9") (pin "1") (pinfunction "1_1") (pintype "passive"))
      (node (ref "U2") (pin "1") (pinfunction "G_1") (pintype "passive"))
    )
    (net (code "66") (name "Net-(U3-D)") (class "Default")
      (node (ref "J13") (pin "2") (pinfunction "2_2") (pintype "passive"))
      (node (ref "LED6") (pin "C") (pinfunction "C_C") (pintype "passive"))
      (node (ref "U3") (pin "3") (pinfunction "D_3") (pintype "passive"))
      (node (ref "U4") (pin "3") (pinfunction "D_3") (pintype "passive"))
    )
    (net (code "67") (name "Net-(U3-G)") (class "Default")
      (node (ref "R13") (pin "1") (pinfunction "1_1") (pintype "passive"))
      (node (ref "R14") (pin "2") (pinfunction "2_2") (pintype "passive"))
      (node (ref "U3") (pin "1") (pinfunction "G_1") (pintype "passive"))
      (node (ref "U4") (pin "1") (pinfunction "G_1") (pintype "passive"))
    )
    (net (code "68") (name "Net-(U5-D)") (class "Default")
      (node (ref "J14") (pin "2") (pinfunction "2_2") (pintype "passive"))
      (node (ref "R23") (pin "1") (pinfunction "1_1") (pintype "passive"))
      (node (ref "U5") (pin "3") (pinfunction "D_3") (pintype "passive"))
    )
    (net (code "69") (name "Net-(U5-G)") (class "Default")
      (node (ref "R21") (pin "1") (pinfunction "1_1") (pintype "passive"))
      (node (ref "R22") (pin "2") (pinfunction "2_2") (pintype "passive"))
      (node (ref "U5") (pin "1") (pinfunction "G_1") (pintype "passive"))
    )
    (net (code "70") (name "Net-(U7-BOOT)") (class "Default")
      (node (ref "C6") (pin "1") (pinfunction "1_1") (pintype "passive"))
      (node (ref "U7") (pin "6") (pinfunction "BOOT_6") (pintype "power_in"))
    )
    (net (code "71") (name "Net-(U7-FB)") (class "Default")
      (node (ref "C7") (pin "2") (pinfunction "2_2") (pintype "passive"))
      (node (ref "R24") (pin "1") (pinfunction "1_1") (pintype "passive"))
      (node (ref "R29") (pin "2") (pinfunction "2_2") (pintype "passive"))
      (node (ref "U7") (pin "4") (pinfunction "FB_4") (pintype "input"))
    )
    (net (code "72") (name "Net-(U7-SW)") (class "Default")
      (node (ref "C6") (pin "2") (pinfunction "2_2") (pintype "passive"))
      (node (ref "L1") (pin "2") (pinfunction "2_2") (pintype "passive"))
      (node (ref "U7") (pin "2") (pinfunction "SW_2") (pintype "power_in"))
    )
    (net (code "73") (name "Net-(V1-K)") (class "Default")
      (node (ref "LED5") (pin "A") (pinfunction "A_A") (pintype "passive"))
      (node (ref "V1") (pin "C") (pinfunction "K_C") (pintype "bidirectional"))
    )
    (net (code "74") (name "Net-(V2-K)") (class "Default")
      (node (ref "LED1") (pin "A") (pinfunction "A_A") (pintype "passive"))
      (node (ref "V2") (pin "C") (pinfunction "K_C") (pintype "bidirectional"))
    )
    (net (code "75") (name "unconnected-(SV1-Pad1)") (class "Default")
      (node (ref "SV1") (pin "1") (pinfunction "1_1") (pintype "passive"))
    )
    (net (code "76") (name "unconnected-(SV1-Pad3)") (class "Default")
      (node (ref "SV1") (pin "3") (pinfunction "3_3") (pintype "passive"))
    )
    (net (code "77") (name "unconnected-(SV1-Pad5)") (class "Default")
      (node (ref "SV1") (pin "5") (pinfunction "5_5") (pintype "passive"))
    )
    (net (code "78") (name "unconnected-(SV1-Pad7)") (class "Default")
      (node (ref "SV1") (pin "7") (pinfunction "7_7") (pintype "passive"))
    )
    (net (code "79") (name "unconnected-(SV1-Pad11)") (class "Default")
      (node (ref "SV1") (pin "11") (pinfunction "11_11") (pintype "passive"))
    )
    (net (code "80") (name "unconnected-(SV1-Pad12)") (class "Default")
      (node (ref "SV1") (pin "12") (pinfunction "12_12") (pintype "passive"))
    )
    (net (code "81") (name "unconnected-(SV1-Pad13)") (class "Default")
      (node (ref "SV1") (pin "13") (pinfunction "13_13") (pintype "passive"))
    )
    (net (code "82") (name "unconnected-(SV1-Pad15)") (class "Default")
      (node (ref "SV1") (pin "15") (pinfunction "15_15") (pintype "passive"))
    )
    (net (code "83") (name "unconnected-(SV1-Pad16)") (class "Default")
      (node (ref "SV1") (pin "16") (pinfunction "16_16") (pintype "passive"))
    )
    (net (code "84") (name "unconnected-(SV1-Pad17)") (class "Default")
      (node (ref "SV1") (pin "17") (pinfunction "17_17") (pintype "passive"))
    )
    (net (code "85") (name "unconnected-(SV1-Pad18)") (class "Default")
      (node (ref "SV1") (pin "18") (pinfunction "18_18") (pintype "passive"))
    )
    (net (code "86") (name "unconnected-(SV1-Pad19)") (class "Default")
      (node (ref "SV1") (pin "19") (pinfunction "19_19") (pintype "passive"))
    )
    (net (code "87") (name "unconnected-(SV1-Pad21)") (class "Default")
      (node (ref "SV1") (pin "21") (pinfunction "21_21") (pintype "passive"))
    )
    (net (code "88") (name "unconnected-(SV1-Pad22)") (class "Default")
      (node (ref "SV1") (pin "22") (pinfunction "22_22") (pintype "passive"))
    )
    (net (code "89") (name "unconnected-(SV1-Pad23)") (class "Default")
      (node (ref "SV1") (pin "23") (pinfunction "23_23") (pintype "passive"))
    )
    (net (code "90") (name "unconnected-(SV1-Pad24)") (class "Default")
      (node (ref "SV1") (pin "24") (pinfunction "24_24") (pintype "passive"))
    )
    (net (code "91") (name "unconnected-(SV1-Pad26)") (class "Default")
      (node (ref "SV1") (pin "26") (pinfunction "26_26") (pintype "passive"))
    )
    (net (code "92") (name "unconnected-(SV1-Pad27)") (class "Default")
      (node (ref "SV1") (pin "27") (pinfunction "27_27") (pintype "passive"))
    )
    (net (code "93") (name "unconnected-(SV1-Pad28)") (class "Default")
      (node (ref "SV1") (pin "28") (pinfunction "28_28") (pintype "passive"))
    )
    (net (code "94") (name "unconnected-(SV1-Pad29)") (class "Default")
      (node (ref "SV1") (pin "29") (pinfunction "29_29") (pintype "passive"))
    )
    (net (code "95") (name "unconnected-(SV1-Pad31)") (class "Default")
      (node (ref "SV1") (pin "31") (pinfunction "31_31") (pintype "passive"))
    )
    (net (code "96") (name "unconnected-(SV1-Pad32)") (class "Default")
      (node (ref "SV1") (pin "32") (pinfunction "32_32") (pintype "passive"))
    )
    (net (code "97") (name "unconnected-(SV1-Pad33)") (class "Default")
      (node (ref "SV1") (pin "33") (pinfunction "33_33") (pintype "passive"))
    )
    (net (code "98") (name "unconnected-(SV1-Pad35)") (class "Default")
      (node (ref "SV1") (pin "35") (pinfunction "35_35") (pintype "passive"))
    )
    (net (code "99") (name "unconnected-(SV1-Pad36)") (class "Default")
      (node (ref "SV1") (pin "36") (pinfunction "36_36") (pintype "passive"))
    )
    (net (code "100") (name "unconnected-(SV1-Pad37)") (class "Default")
      (node (ref "SV1") (pin "37") (pinfunction "37_37") (pintype "passive"))
    )
    (net (code "101") (name "unconnected-(SV1-Pad38)") (class "Default")
      (node (ref "SV1") (pin "38") (pinfunction "38_38") (pintype "passive"))
    )
    (net (code "102") (name "unconnected-(SV1-Pad40)") (class "Default")
      (node (ref "SV1") (pin "40") (pinfunction "40_40") (pintype "passive"))
    )
    (net (code "103") (name "unconnected-(SV5-Pad3)") (class "Default")
      (node (ref "SV5") (pin "3") (pinfunction "3_3") (pintype "passive"))
    )
    (net (code "104") (name "unconnected-(SV5-Pad21)") (class "Default")
      (node (ref "SV5") (pin "21") (pinfunction "21_21") (pintype "passive"))
    )
    (net (code "105") (name "unconnected-(SV5-Pad22)") (class "Default")
      (node (ref "SV5") (pin "22") (pinfunction "22_22") (pintype "passive"))
    )
    (net (code "106") (name "unconnected-(SV5-Pad23)") (class "Default")
      (node (ref "SV5") (pin "23") (pinfunction "23_23") (pintype "passive"))
    )
    (net (code "107") (name "unconnected-(U$5-3V3(OUT)-Pad36)") (class "Default")
      (node (ref "U$5") (pin "36") (pinfunction "3V3(OUT)_36") (pintype "output"))
    )
    (net (code "108") (name "unconnected-(U$5-RUN-Pad30)") (class "Default")
      (node (ref "U$5") (pin "30") (pinfunction "RUN_30") (pintype "passive"))
    )
    (net (code "109") (name "unconnected-(U7-EN-Pad5)") (class "Default")
      (node (ref "U7") (pin "5") (pinfunction "EN_5") (pintype "input"))
    )
  )
)
